# 40_pin_BB.net
KiCad netlist of a schematic drawn in EAGLE
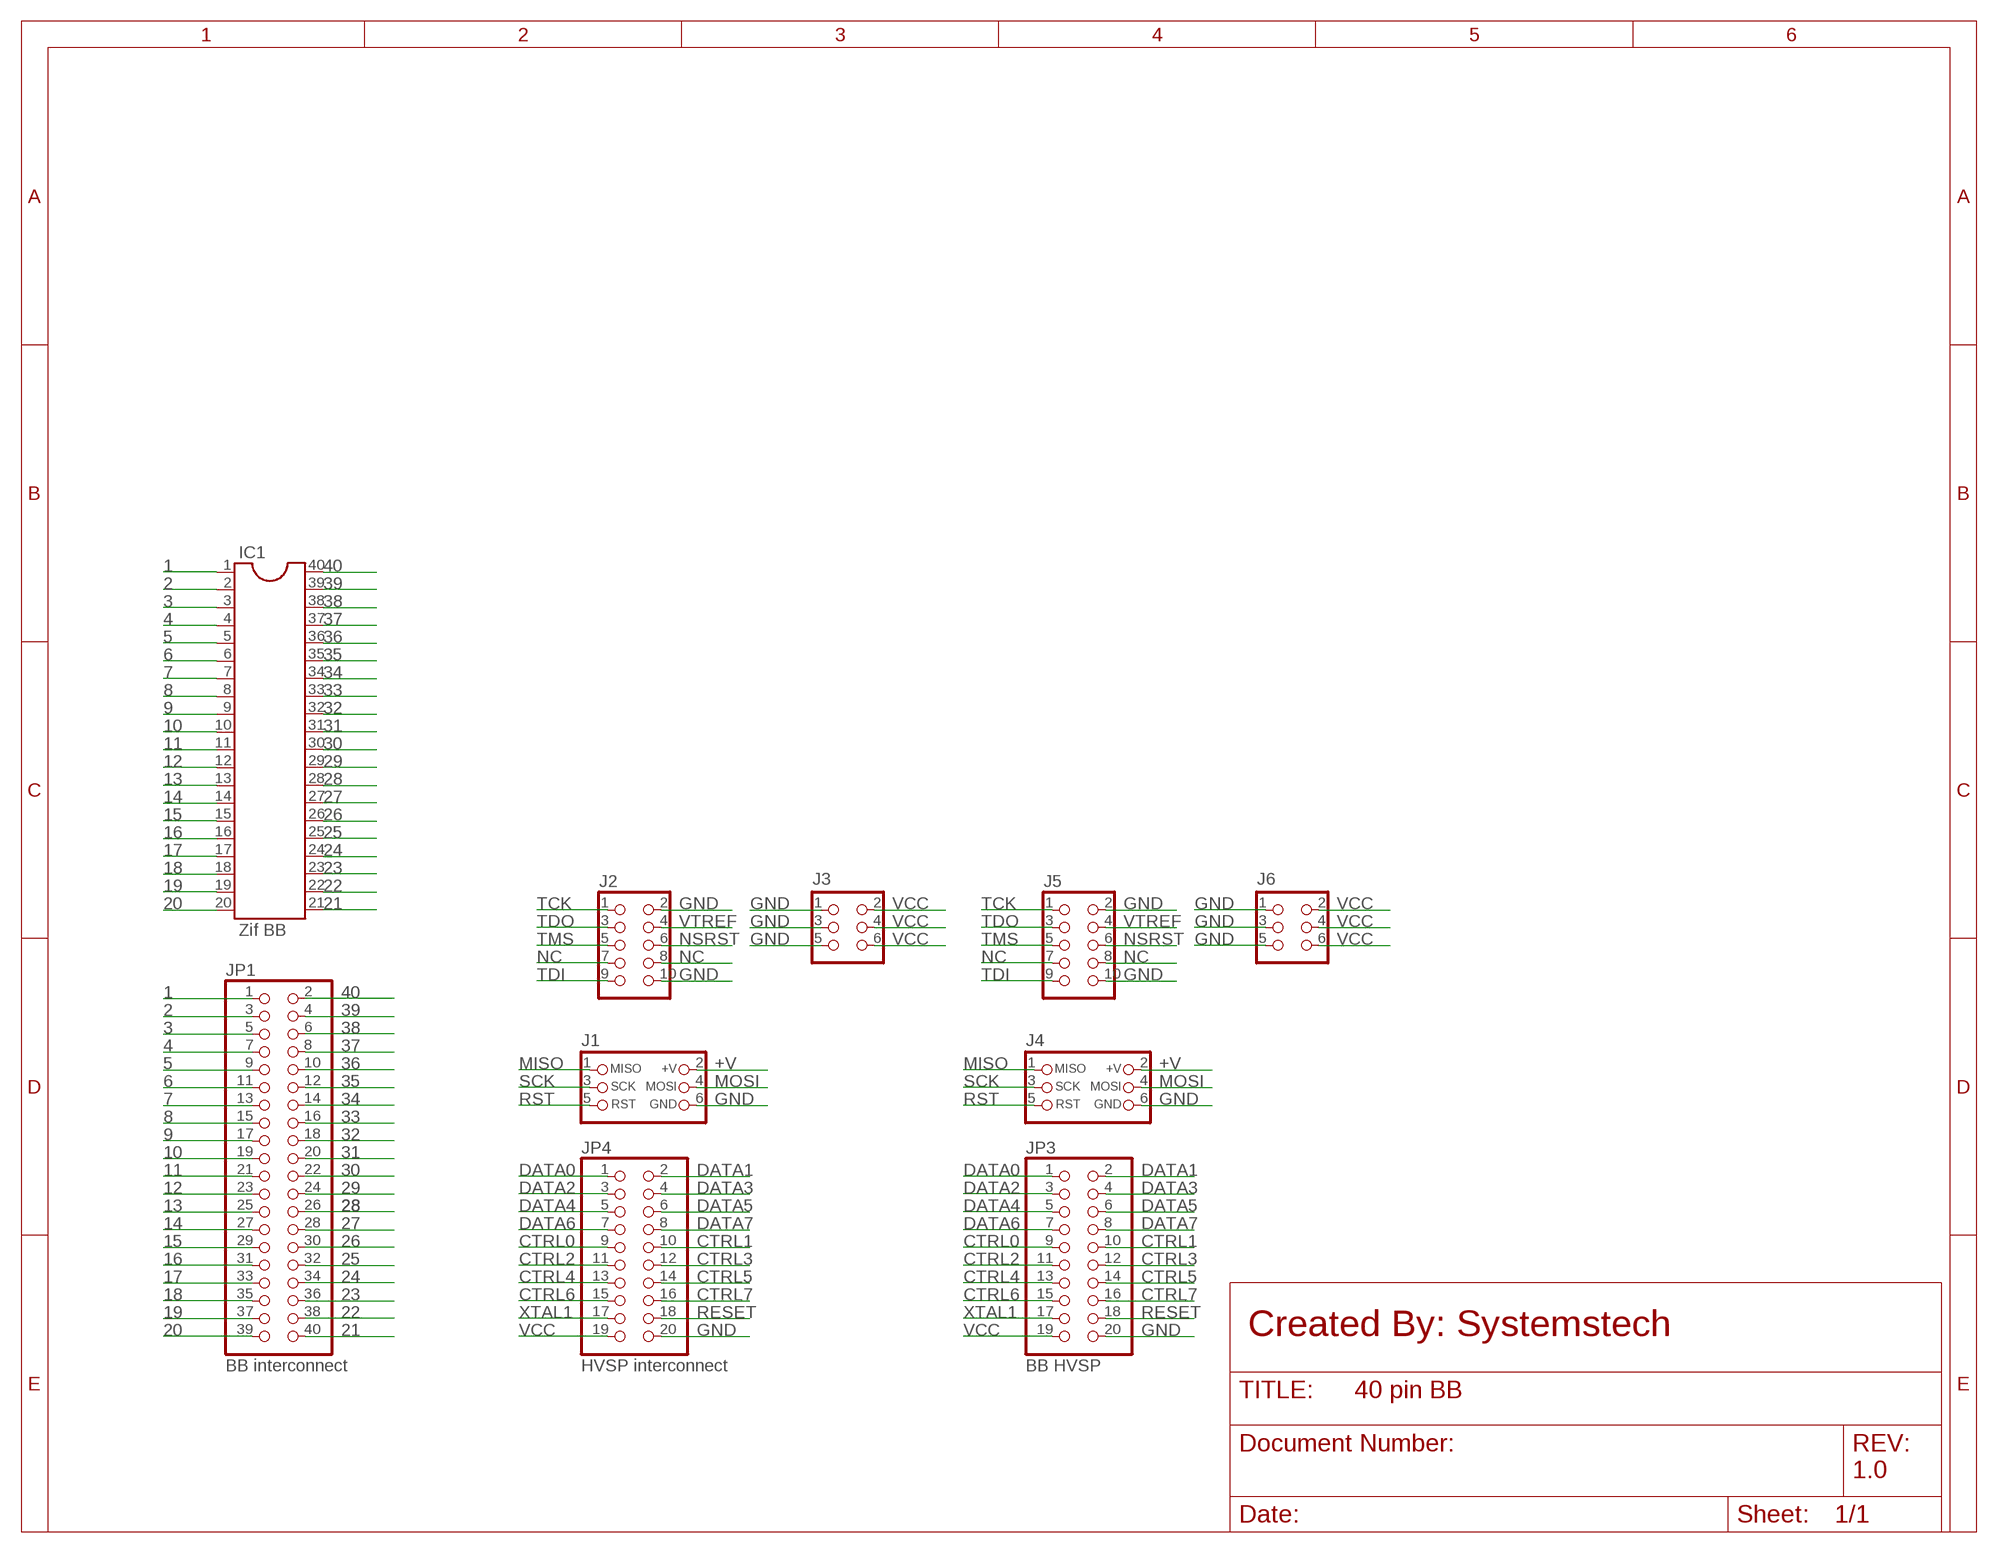
[diagram p0: schematic, sheet 1]

(export (version "E")
  (design (tool "Eeschema 10.0.6"))
  (components
    (comp (ref "IC1")
      (value "Zif BB")
      (footprint "eagle-import:DIL40")
      (libsource (lib "eagle-import") (part "DIL40"))
    )
    (comp (ref "J1")
      (value "CON_HEADER_PRG_AVR_ICSP")
      (footprint "eagle-import:HEADER_PRG_2X03")
      (libsource (lib "eagle-import") (part "CON_HEADER_PRG_AVR_ICSP"))
    )
    (comp (ref "J2")
      (value "CON_HEADER_2X05-PTH")
      (footprint "eagle-import:M2X5")
      (libsource (lib "eagle-import") (part "CON_HEADER_2X05-PTH"))
    )
    (comp (ref "J3")
      (value "CON_HEADER_2X03-PTH")
      (footprint "eagle-import:M2X3")
      (libsource (lib "eagle-import") (part "CON_HEADER_2X03-PTH"))
    )
    (comp (ref "J4")
      (value "CON_HEADER_PRG_AVR_ICSP")
      (footprint "eagle-import:HEADER_PRG_2X03")
      (libsource (lib "eagle-import") (part "CON_HEADER_PRG_AVR_ICSP"))
    )
    (comp (ref "J5")
      (value "CON_HEADER_2X05-PTH")
      (footprint "eagle-import:M2X5")
      (libsource (lib "eagle-import") (part "CON_HEADER_2X05-PTH"))
    )
    (comp (ref "J6")
      (value "CON_HEADER_2X03-PTH")
      (footprint "eagle-import:M2X3")
      (libsource (lib "eagle-import") (part "CON_HEADER_2X03-PTH"))
    )
    (comp (ref "JP1")
      (value "BB interconnect")
      (footprint "eagle-import:2X20")
      (libsource (lib "eagle-import") (part "PINHD-2X20"))
    )
    (comp (ref "JP3")
      (value "BB HVSP")
      (footprint "eagle-import:2X10")
      (libsource (lib "eagle-import") (part "PINHD-2X10"))
    )
    (comp (ref "JP4")
      (value "HVSP interconnect")
      (footprint "eagle-import:2X10")
      (libsource (lib "eagle-import") (part "PINHD-2X10"))
    )
  )
  (nets
    (net (code "1") (name "/+V") (class "Default")
      (node (ref "J1") (pin "2") (pinfunction "+V_2") (pintype "passive"))
      (node (ref "J4") (pin "2") (pinfunction "+V_2") (pintype "passive"))
    )
    (net (code "2") (name "/1") (class "Default")
      (node (ref "IC1") (pin "1") (pinfunction "1_1") (pintype "passive"))
      (node (ref "JP1") (pin "1") (pinfunction "1_1") (pintype "passive"))
    )
    (net (code "3") (name "/2") (class "Default")
      (node (ref "IC1") (pin "2") (pinfunction "2_2") (pintype "passive"))
      (node (ref "JP1") (pin "3") (pinfunction "3_3") (pintype "passive"))
    )
    (net (code "4") (name "/3") (class "Default")
      (node (ref "IC1") (pin "3") (pinfunction "3_3") (pintype "passive"))
      (node (ref "JP1") (pin "5") (pinfunction "5_5") (pintype "passive"))
    )
    (net (code "5") (name "/4") (class "Default")
      (node (ref "IC1") (pin "4") (pinfunction "4_4") (pintype "passive"))
      (node (ref "JP1") (pin "7") (pinfunction "7_7") (pintype "passive"))
    )
    (net (code "6") (name "/5") (class "Default")
      (node (ref "IC1") (pin "5") (pinfunction "5_5") (pintype "passive"))
      (node (ref "JP1") (pin "9") (pinfunction "9_9") (pintype "passive"))
    )
    (net (code "7") (name "/6") (class "Default")
      (node (ref "IC1") (pin "6") (pinfunction "6_6") (pintype "passive"))
      (node (ref "JP1") (pin "11") (pinfunction "11_11") (pintype "passive"))
    )
    (net (code "8") (name "/7") (class "Default")
      (node (ref "IC1") (pin "7") (pinfunction "7_7") (pintype "passive"))
      (node (ref "JP1") (pin "13") (pinfunction "13_13") (pintype "passive"))
    )
    (net (code "9") (name "/8") (class "Default")
      (node (ref "IC1") (pin "8") (pinfunction "8_8") (pintype "passive"))
      (node (ref "JP1") (pin "15") (pinfunction "15_15") (pintype "passive"))
    )
    (net (code "10") (name "/9") (class "Default")
      (node (ref "IC1") (pin "9") (pinfunction "9_9") (pintype "passive"))
      (node (ref "JP1") (pin "17") (pinfunction "17_17") (pintype "passive"))
    )
    (net (code "11") (name "/10") (class "Default")
      (node (ref "IC1") (pin "10") (pinfunction "10_10") (pintype "passive"))
      (node (ref "JP1") (pin "19") (pinfunction "19_19") (pintype "passive"))
    )
    (net (code "12") (name "/11") (class "Default")
      (node (ref "IC1") (pin "11") (pinfunction "11_11") (pintype "passive"))
      (node (ref "JP1") (pin "21") (pinfunction "21_21") (pintype "passive"))
    )
    (net (code "13") (name "/12") (class "Default")
      (node (ref "IC1") (pin "12") (pinfunction "12_12") (pintype "passive"))
      (node (ref "JP1") (pin "23") (pinfunction "23_23") (pintype "passive"))
    )
    (net (code "14") (name "/13") (class "Default")
      (node (ref "IC1") (pin "13") (pinfunction "13_13") (pintype "passive"))
      (node (ref "JP1") (pin "25") (pinfunction "25_25") (pintype "passive"))
    )
    (net (code "15") (name "/14") (class "Default")
      (node (ref "IC1") (pin "14") (pinfunction "14_14") (pintype "passive"))
      (node (ref "JP1") (pin "27") (pinfunction "27_27") (pintype "passive"))
    )
    (net (code "16") (name "/15") (class "Default")
      (node (ref "IC1") (pin "15") (pinfunction "15_15") (pintype "passive"))
      (node (ref "JP1") (pin "29") (pinfunction "29_29") (pintype "passive"))
    )
    (net (code "17") (name "/16") (class "Default")
      (node (ref "IC1") (pin "16") (pinfunction "16_16") (pintype "passive"))
      (node (ref "JP1") (pin "31") (pinfunction "31_31") (pintype "passive"))
    )
    (net (code "18") (name "/17") (class "Default")
      (node (ref "IC1") (pin "17") (pinfunction "17_17") (pintype "passive"))
      (node (ref "JP1") (pin "33") (pinfunction "33_33") (pintype "passive"))
    )
    (net (code "19") (name "/18") (class "Default")
      (node (ref "IC1") (pin "18") (pinfunction "18_18") (pintype "passive"))
      (node (ref "JP1") (pin "35") (pinfunction "35_35") (pintype "passive"))
    )
    (net (code "20") (name "/19") (class "Default")
      (node (ref "IC1") (pin "19") (pinfunction "19_19") (pintype "passive"))
      (node (ref "JP1") (pin "37") (pinfunction "37_37") (pintype "passive"))
    )
    (net (code "21") (name "/20") (class "Default")
      (node (ref "IC1") (pin "20") (pinfunction "20_20") (pintype "passive"))
      (node (ref "JP1") (pin "39") (pinfunction "39_39") (pintype "passive"))
    )
    (net (code "22") (name "/21") (class "Default")
      (node (ref "IC1") (pin "21") (pinfunction "21_21") (pintype "passive"))
      (node (ref "JP1") (pin "40") (pinfunction "40_40") (pintype "passive"))
    )
    (net (code "23") (name "/22") (class "Default")
      (node (ref "IC1") (pin "22") (pinfunction "22_22") (pintype "passive"))
      (node (ref "JP1") (pin "38") (pinfunction "38_38") (pintype "passive"))
    )
    (net (code "24") (name "/23") (class "Default")
      (node (ref "IC1") (pin "23") (pinfunction "23_23") (pintype "passive"))
      (node (ref "JP1") (pin "36") (pinfunction "36_36") (pintype "passive"))
    )
    (net (code "25") (name "/24") (class "Default")
      (node (ref "IC1") (pin "24") (pinfunction "24_24") (pintype "passive"))
      (node (ref "JP1") (pin "34") (pinfunction "34_34") (pintype "passive"))
    )
    (net (code "26") (name "/25") (class "Default")
      (node (ref "IC1") (pin "25") (pinfunction "25_25") (pintype "passive"))
      (node (ref "JP1") (pin "32") (pinfunction "32_32") (pintype "passive"))
    )
    (net (code "27") (name "/26") (class "Default")
      (node (ref "IC1") (pin "26") (pinfunction "26_26") (pintype "passive"))
      (node (ref "JP1") (pin "30") (pinfunction "30_30") (pintype "passive"))
    )
    (net (code "28") (name "/27") (class "Default")
      (node (ref "IC1") (pin "27") (pinfunction "27_27") (pintype "passive"))
      (node (ref "JP1") (pin "28") (pinfunction "28_28") (pintype "passive"))
    )
    (net (code "29") (name "/28") (class "Default")
      (node (ref "IC1") (pin "28") (pinfunction "28_28") (pintype "passive"))
      (node (ref "JP1") (pin "26") (pinfunction "26_26") (pintype "passive"))
    )
    (net (code "30") (name "/29") (class "Default")
      (node (ref "IC1") (pin "29") (pinfunction "29_29") (pintype "passive"))
      (node (ref "JP1") (pin "24") (pinfunction "24_24") (pintype "passive"))
    )
    (net (code "31") (name "/30") (class "Default")
      (node (ref "IC1") (pin "30") (pinfunction "30_30") (pintype "passive"))
      (node (ref "JP1") (pin "22") (pinfunction "22_22") (pintype "passive"))
    )
    (net (code "32") (name "/31") (class "Default")
      (node (ref "IC1") (pin "31") (pinfunction "31_31") (pintype "passive"))
      (node (ref "JP1") (pin "20") (pinfunction "20_20") (pintype "passive"))
    )
    (net (code "33") (name "/32") (class "Default")
      (node (ref "IC1") (pin "32") (pinfunction "32_32") (pintype "passive"))
      (node (ref "JP1") (pin "18") (pinfunction "18_18") (pintype "passive"))
    )
    (net (code "34") (name "/33") (class "Default")
      (node (ref "IC1") (pin "33") (pinfunction "33_33") (pintype "passive"))
      (node (ref "JP1") (pin "16") (pinfunction "16_16") (pintype "passive"))
    )
    (net (code "35") (name "/34") (class "Default")
      (node (ref "IC1") (pin "34") (pinfunction "34_34") (pintype "passive"))
      (node (ref "JP1") (pin "14") (pinfunction "14_14") (pintype "passive"))
    )
    (net (code "36") (name "/35") (class "Default")
      (node (ref "IC1") (pin "35") (pinfunction "35_35") (pintype "passive"))
      (node (ref "JP1") (pin "12") (pinfunction "12_12") (pintype "passive"))
    )
    (net (code "37") (name "/36") (class "Default")
      (node (ref "IC1") (pin "36") (pinfunction "36_36") (pintype "passive"))
      (node (ref "JP1") (pin "10") (pinfunction "10_10") (pintype "passive"))
    )
    (net (code "38") (name "/37") (class "Default")
      (node (ref "IC1") (pin "37") (pinfunction "37_37") (pintype "passive"))
      (node (ref "JP1") (pin "8") (pinfunction "8_8") (pintype "passive"))
    )
    (net (code "39") (name "/38") (class "Default")
      (node (ref "IC1") (pin "38") (pinfunction "38_38") (pintype "passive"))
      (node (ref "JP1") (pin "6") (pinfunction "6_6") (pintype "passive"))
    )
    (net (code "40") (name "/39") (class "Default")
      (node (ref "IC1") (pin "39") (pinfunction "39_39") (pintype "passive"))
      (node (ref "JP1") (pin "4") (pinfunction "4_4") (pintype "passive"))
    )
    (net (code "41") (name "/40") (class "Default")
      (node (ref "IC1") (pin "40") (pinfunction "40_40") (pintype "passive"))
      (node (ref "JP1") (pin "2") (pinfunction "2_2") (pintype "passive"))
    )
    (net (code "42") (name "/CTRL0") (class "Default")
      (node (ref "JP3") (pin "9") (pinfunction "9_9") (pintype "passive"))
      (node (ref "JP4") (pin "9") (pinfunction "9_9") (pintype "passive"))
    )
    (net (code "43") (name "/CTRL1") (class "Default")
      (node (ref "JP3") (pin "10") (pinfunction "10_10") (pintype "passive"))
      (node (ref "JP4") (pin "10") (pinfunction "10_10") (pintype "passive"))
    )
    (net (code "44") (name "/CTRL2") (class "Default")
      (node (ref "JP3") (pin "11") (pinfunction "11_11") (pintype "passive"))
      (node (ref "JP4") (pin "11") (pinfunction "11_11") (pintype "passive"))
    )
    (net (code "45") (name "/CTRL3") (class "Default")
      (node (ref "JP3") (pin "12") (pinfunction "12_12") (pintype "passive"))
      (node (ref "JP4") (pin "12") (pinfunction "12_12") (pintype "passive"))
    )
    (net (code "46") (name "/CTRL4") (class "Default")
      (node (ref "JP3") (pin "13") (pinfunction "13_13") (pintype "passive"))
      (node (ref "JP4") (pin "13") (pinfunction "13_13") (pintype "passive"))
    )
    (net (code "47") (name "/CTRL5") (class "Default")
      (node (ref "JP3") (pin "14") (pinfunction "14_14") (pintype "passive"))
      (node (ref "JP4") (pin "14") (pinfunction "14_14") (pintype "passive"))
    )
    (net (code "48") (name "/CTRL6") (class "Default")
      (node (ref "JP3") (pin "15") (pinfunction "15_15") (pintype "passive"))
      (node (ref "JP4") (pin "15") (pinfunction "15_15") (pintype "passive"))
    )
    (net (code "49") (name "/CTRL7") (class "Default")
      (node (ref "JP3") (pin "16") (pinfunction "16_16") (pintype "passive"))
      (node (ref "JP4") (pin "16") (pinfunction "16_16") (pintype "passive"))
    )
    (net (code "50") (name "/DATA0") (class "Default")
      (node (ref "JP3") (pin "1") (pinfunction "1_1") (pintype "passive"))
      (node (ref "JP4") (pin "1") (pinfunction "1_1") (pintype "passive"))
    )
    (net (code "51") (name "/DATA1") (class "Default")
      (node (ref "JP3") (pin "2") (pinfunction "2_2") (pintype "passive"))
      (node (ref "JP4") (pin "2") (pinfunction "2_2") (pintype "passive"))
    )
    (net (code "52") (name "/DATA2") (class "Default")
      (node (ref "JP3") (pin "3") (pinfunction "3_3") (pintype "passive"))
      (node (ref "JP4") (pin "3") (pinfunction "3_3") (pintype "passive"))
    )
    (net (code "53") (name "/DATA3") (class "Default")
      (node (ref "JP3") (pin "4") (pinfunction "4_4") (pintype "passive"))
      (node (ref "JP4") (pin "4") (pinfunction "4_4") (pintype "passive"))
    )
    (net (code "54") (name "/DATA4") (class "Default")
      (node (ref "JP3") (pin "5") (pinfunction "5_5") (pintype "passive"))
      (node (ref "JP4") (pin "5") (pinfunction "5_5") (pintype "passive"))
    )
    (net (code "55") (name "/DATA5") (class "Default")
      (node (ref "JP3") (pin "6") (pinfunction "6_6") (pintype "passive"))
      (node (ref "JP4") (pin "6") (pinfunction "6_6") (pintype "passive"))
    )
    (net (code "56") (name "/DATA6") (class "Default")
      (node (ref "JP3") (pin "7") (pinfunction "7_7") (pintype "passive"))
      (node (ref "JP4") (pin "7") (pinfunction "7_7") (pintype "passive"))
    )
    (net (code "57") (name "/DATA7") (class "Default")
      (node (ref "JP3") (pin "8") (pinfunction "8_8") (pintype "passive"))
      (node (ref "JP4") (pin "8") (pinfunction "8_8") (pintype "passive"))
    )
    (net (code "58") (name "/GND") (class "Default")
      (node (ref "J1") (pin "6") (pinfunction "GND_6") (pintype "passive"))
      (node (ref "J2") (pin "10") (pinfunction "10_10") (pintype "passive"))
      (node (ref "J2") (pin "2") (pinfunction "2_2") (pintype "passive"))
      (node (ref "J3") (pin "1") (pinfunction "1_1") (pintype "passive"))
      (node (ref "J3") (pin "3") (pinfunction "3_3") (pintype "passive"))
      (node (ref "J3") (pin "5") (pinfunction "5_5") (pintype "passive"))
      (node (ref "J4") (pin "6") (pinfunction "GND_6") (pintype "passive"))
      (node (ref "J5") (pin "10") (pinfunction "10_10") (pintype "passive"))
      (node (ref "J5") (pin "2") (pinfunction "2_2") (pintype "passive"))
      (node (ref "J6") (pin "1") (pinfunction "1_1") (pintype "passive"))
      (node (ref "J6") (pin "3") (pinfunction "3_3") (pintype "passive"))
      (node (ref "J6") (pin "5") (pinfunction "5_5") (pintype "passive"))
      (node (ref "JP3") (pin "20") (pinfunction "20_20") (pintype "passive"))
      (node (ref "JP4") (pin "20") (pinfunction "20_20") (pintype "passive"))
    )
    (net (code "59") (name "/MISO") (class "Default")
      (node (ref "J1") (pin "1") (pinfunction "MISO_1") (pintype "passive"))
      (node (ref "J4") (pin "1") (pinfunction "MISO_1") (pintype "passive"))
    )
    (net (code "60") (name "/MOSI") (class "Default")
      (node (ref "J1") (pin "4") (pinfunction "MOSI_4") (pintype "passive"))
      (node (ref "J4") (pin "4") (pinfunction "MOSI_4") (pintype "passive"))
    )
    (net (code "61") (name "/NC") (class "Default")
      (node (ref "J2") (pin "7") (pinfunction "7_7") (pintype "passive"))
      (node (ref "J2") (pin "8") (pinfunction "8_8") (pintype "passive"))
      (node (ref "J5") (pin "7") (pinfunction "7_7") (pintype "passive"))
      (node (ref "J5") (pin "8") (pinfunction "8_8") (pintype "passive"))
    )
    (net (code "62") (name "/NSRST") (class "Default")
      (node (ref "J2") (pin "6") (pinfunction "6_6") (pintype "passive"))
      (node (ref "J5") (pin "6") (pinfunction "6_6") (pintype "passive"))
    )
    (net (code "63") (name "/RESET") (class "Default")
      (node (ref "JP3") (pin "18") (pinfunction "18_18") (pintype "passive"))
      (node (ref "JP4") (pin "18") (pinfunction "18_18") (pintype "passive"))
    )
    (net (code "64") (name "/RST") (class "Default")
      (node (ref "J1") (pin "5") (pinfunction "RST_5") (pintype "passive"))
      (node (ref "J4") (pin "5") (pinfunction "RST_5") (pintype "passive"))
    )
    (net (code "65") (name "/SCK") (class "Default")
      (node (ref "J1") (pin "3") (pinfunction "SCK_3") (pintype "passive"))
      (node (ref "J4") (pin "3") (pinfunction "SCK_3") (pintype "passive"))
    )
    (net (code "66") (name "/TCK") (class "Default")
      (node (ref "J2") (pin "1") (pinfunction "1_1") (pintype "passive"))
      (node (ref "J5") (pin "1") (pinfunction "1_1") (pintype "passive"))
    )
    (net (code "67") (name "/TDI") (class "Default")
      (node (ref "J2") (pin "9") (pinfunction "9_9") (pintype "passive"))
      (node (ref "J5") (pin "9") (pinfunction "9_9") (pintype "passive"))
    )
    (net (code "68") (name "/TDO") (class "Default")
      (node (ref "J2") (pin "3") (pinfunction "3_3") (pintype "passive"))
      (node (ref "J5") (pin "3") (pinfunction "3_3") (pintype "passive"))
    )
    (net (code "69") (name "/TMS") (class "Default")
      (node (ref "J2") (pin "5") (pinfunction "5_5") (pintype "passive"))
      (node (ref "J5") (pin "5") (pinfunction "5_5") (pintype "passive"))
    )
    (net (code "70") (name "/VCC") (class "Default")
      (node (ref "J3") (pin "2") (pinfunction "2_2") (pintype "passive"))
      (node (ref "J3") (pin "4") (pinfunction "4_4") (pintype "passive"))
      (node (ref "J3") (pin "6") (pinfunction "6_6") (pintype "passive"))
      (node (ref "J6") (pin "2") (pinfunction "2_2") (pintype "passive"))
      (node (ref "J6") (pin "4") (pinfunction "4_4") (pintype "passive"))
      (node (ref "J6") (pin "6") (pinfunction "6_6") (pintype "passive"))
      (node (ref "JP3") (pin "19") (pinfunction "19_19") (pintype "passive"))
      (node (ref "JP4") (pin "19") (pinfunction "19_19") (pintype "passive"))
    )
    (net (code "71") (name "/VTREF") (class "Default")
      (node (ref "J2") (pin "4") (pinfunction "4_4") (pintype "passive"))
      (node (ref "J5") (pin "4") (pinfunction "4_4") (pintype "passive"))
    )
    (net (code "72") (name "/XTAL1") (class "Default")
      (node (ref "JP3") (pin "17") (pinfunction "17_17") (pintype "passive"))
      (node (ref "JP4") (pin "17") (pinfunction "17_17") (pintype "passive"))
    )
  )
)
